# COM-TopLevel.net
KiCad netlist of a schematic drawn in Altium Designer
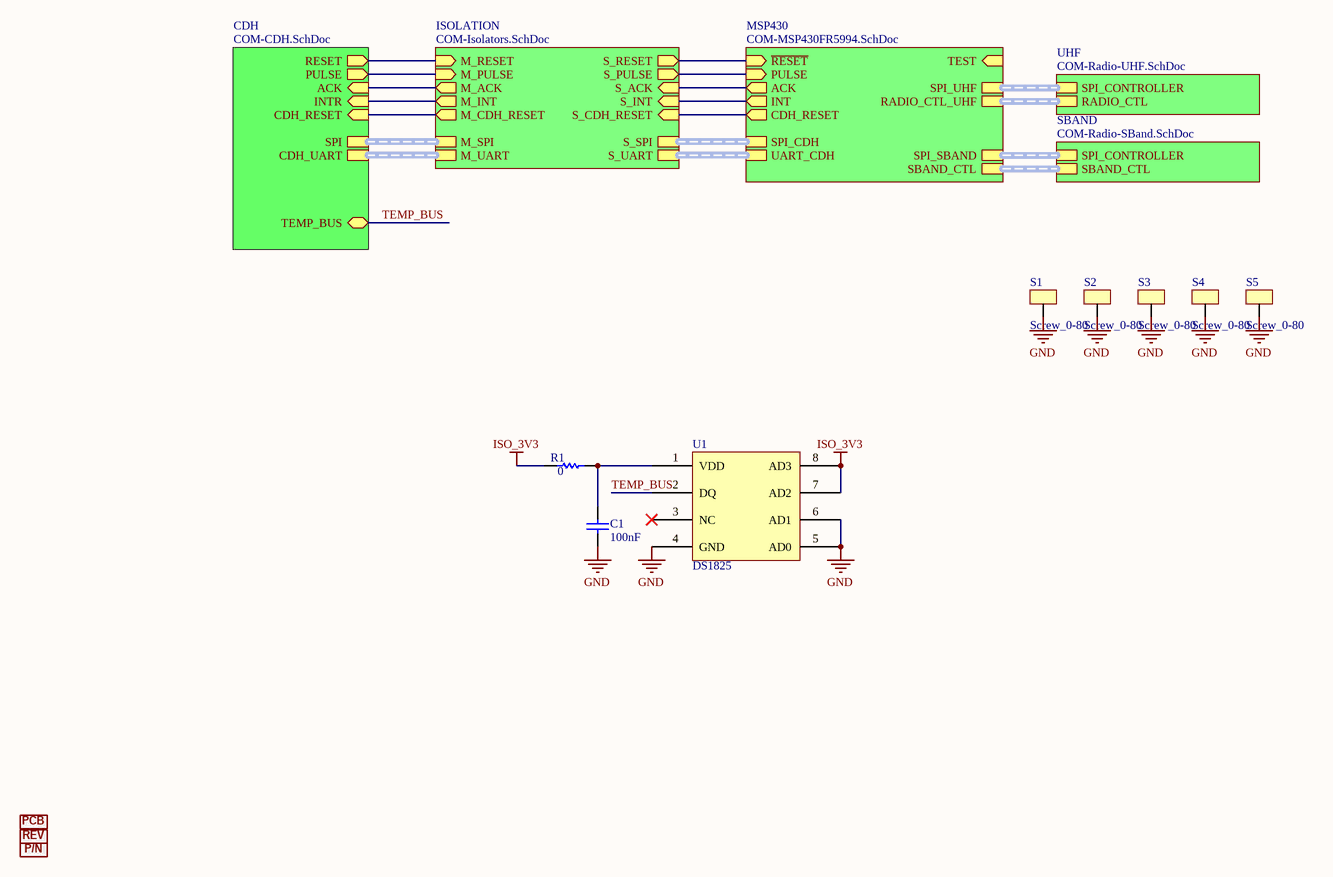
[diagram p0: COM-TopLevel.SchDoc]

(export (version "E")
  (design (tool "Eeschema 10.0.6"))
  (components
    (comp (ref "C1")
      (value "C0603C104J3RACAUTO")
      (footprint "1608[0603]")
      (description "MLCC 1608(0603) X7R 100NF 10% 50")
      (fields
        (field (name "CAPACITANCE") "100nF")
        (field (name "VOLTAGE") "50V")
        (field (name "PARTNUMBER") "CGA2B3X7R1H104K050BB")
      )
      (libsource (lib "PolarCube") (part "Cap"))
    )
    (comp (ref "INFO1")
      (value "Info_Board")
      (footprint "Info_Board")
      (description "Board Name, Engineer, Date")
      (fields (field (name "PARTNUMBER") "Board-Info") (field (name "MANUFACTURER") "COSGC"))
      (libsource (lib "PolarCube") (part "Info_Board"))
    )
    (comp (ref "INFO2")
      (value "Info_Revision")
      (footprint "Info_Revision")
      (description "Version, Rev, Flight Qualified")
      (fields (field (name "PARTNUMBER") "Board-Version") (field (name "MANUFACTURER") "COSGC"))
      (libsource (lib "PolarCube") (part "Info_Revision"))
    )
    (comp (ref "INFO3")
      (value "Info_PartNumber")
      (footprint "Info_PartNumber")
      (description "ALL-STAR Part Number")
      (fields (field (name "PARTNUMBER") "Board-PartNumber") (field (name "MANUFACTURER") "COSGC"))
      (libsource (lib "PolarCube") (part "Info_PartNumber"))
    )
    (comp (ref "R1")
      (value "CRCW06030000Z0EAC")
      (footprint "1608[0603]")
      (description "RES SMD 0 OHM JUMP 1/10W 0603")
      (fields
        (field (name "RESISTANCE") "0")
        (field (name "PARTNUMBER") "CRCW04020000Z0ED")
        (field (name "MANUFACTURER") "Vishay")
      )
      (libsource (lib "PolarCube") (part "Res"))
    )
    (comp (ref "S1")
      (value "Screw_0-80")
      (footprint "Screw_0-80")
      (libsource (lib "Cesium_3") (part "Screw_0-80"))
    )
    (comp (ref "S2")
      (value "Screw_0-80")
      (footprint "Screw_0-80")
      (libsource (lib "Cesium_3") (part "Screw_0-80"))
    )
    (comp (ref "S3")
      (value "Screw_0-80")
      (footprint "Screw_0-80")
      (libsource (lib "Cesium_3") (part "Screw_0-80"))
    )
    (comp (ref "S4")
      (value "Screw_0-80")
      (footprint "Screw_0-80")
      (libsource (lib "Cesium_3") (part "Screw_0-80"))
    )
    (comp (ref "S5")
      (value "Screw_0-80")
      (footprint "Screw_0-80")
      (libsource (lib "Cesium_3") (part "Screw_0-80"))
    )
    (comp (ref "U1")
      (value "DS1825")
      (footprint "DS1825")
      (description "IC THERMOMETER DIGITAL 8-USOP")
      (fields (field (name "PARTNUMBER") "DS1825U+") (field (name "MANUFACTURER") "Maxim"))
      (libsource (lib "PolarCube") (part "DS1825"))
    )
  )
  (nets
    (net (code "19") (name "/TEMP_BUS") (class "Default")
      (node (ref "U1") (pin "2") (pinfunction "DQ_2") (pintype "passive"))
    )
    (net (code "21") (name "GND") (class "Default")
      (node (ref "C1") (pin "2") (pinfunction "2_2") (pintype "passive"))
      (node (ref "S1") (pin "1") (pinfunction "1_1") (pintype "passive"))
      (node (ref "S2") (pin "1") (pinfunction "1_1") (pintype "passive"))
      (node (ref "S3") (pin "1") (pinfunction "1_1") (pintype "passive"))
      (node (ref "S4") (pin "1") (pinfunction "1_1") (pintype "passive"))
      (node (ref "S5") (pin "1") (pinfunction "1_1") (pintype "passive"))
      (node (ref "U1") (pin "4") (pinfunction "GND_4") (pintype "passive"))
      (node (ref "U1") (pin "5") (pinfunction "AD0_5") (pintype "passive"))
      (node (ref "U1") (pin "6") (pinfunction "AD1_6") (pintype "passive"))
    )
    (net (code "22") (name "ISO_3V3") (class "Default")
      (node (ref "R1") (pin "1") (pinfunction "1_1") (pintype "passive"))
      (node (ref "U1") (pin "7") (pinfunction "AD2_7") (pintype "passive"))
      (node (ref "U1") (pin "8") (pinfunction "AD3_8") (pintype "passive"))
    )
    (net (code "23") (name "Net-(U1-VDD)") (class "Default")
      (node (ref "C1") (pin "1") (pinfunction "1_1") (pintype "passive"))
      (node (ref "R1") (pin "2") (pinfunction "2_2") (pintype "passive"))
      (node (ref "U1") (pin "1") (pinfunction "VDD_1") (pintype "power_in"))
    )
    (net (code "24") (name "unconnected-(U1-NC-Pad3)") (class "Default")
      (node (ref "U1") (pin "3") (pinfunction "NC_3") (pintype "passive+no_connect"))
    )
  )
)
